# APM_BLE.net
KiCad netlist of a schematic drawn in EAGLE
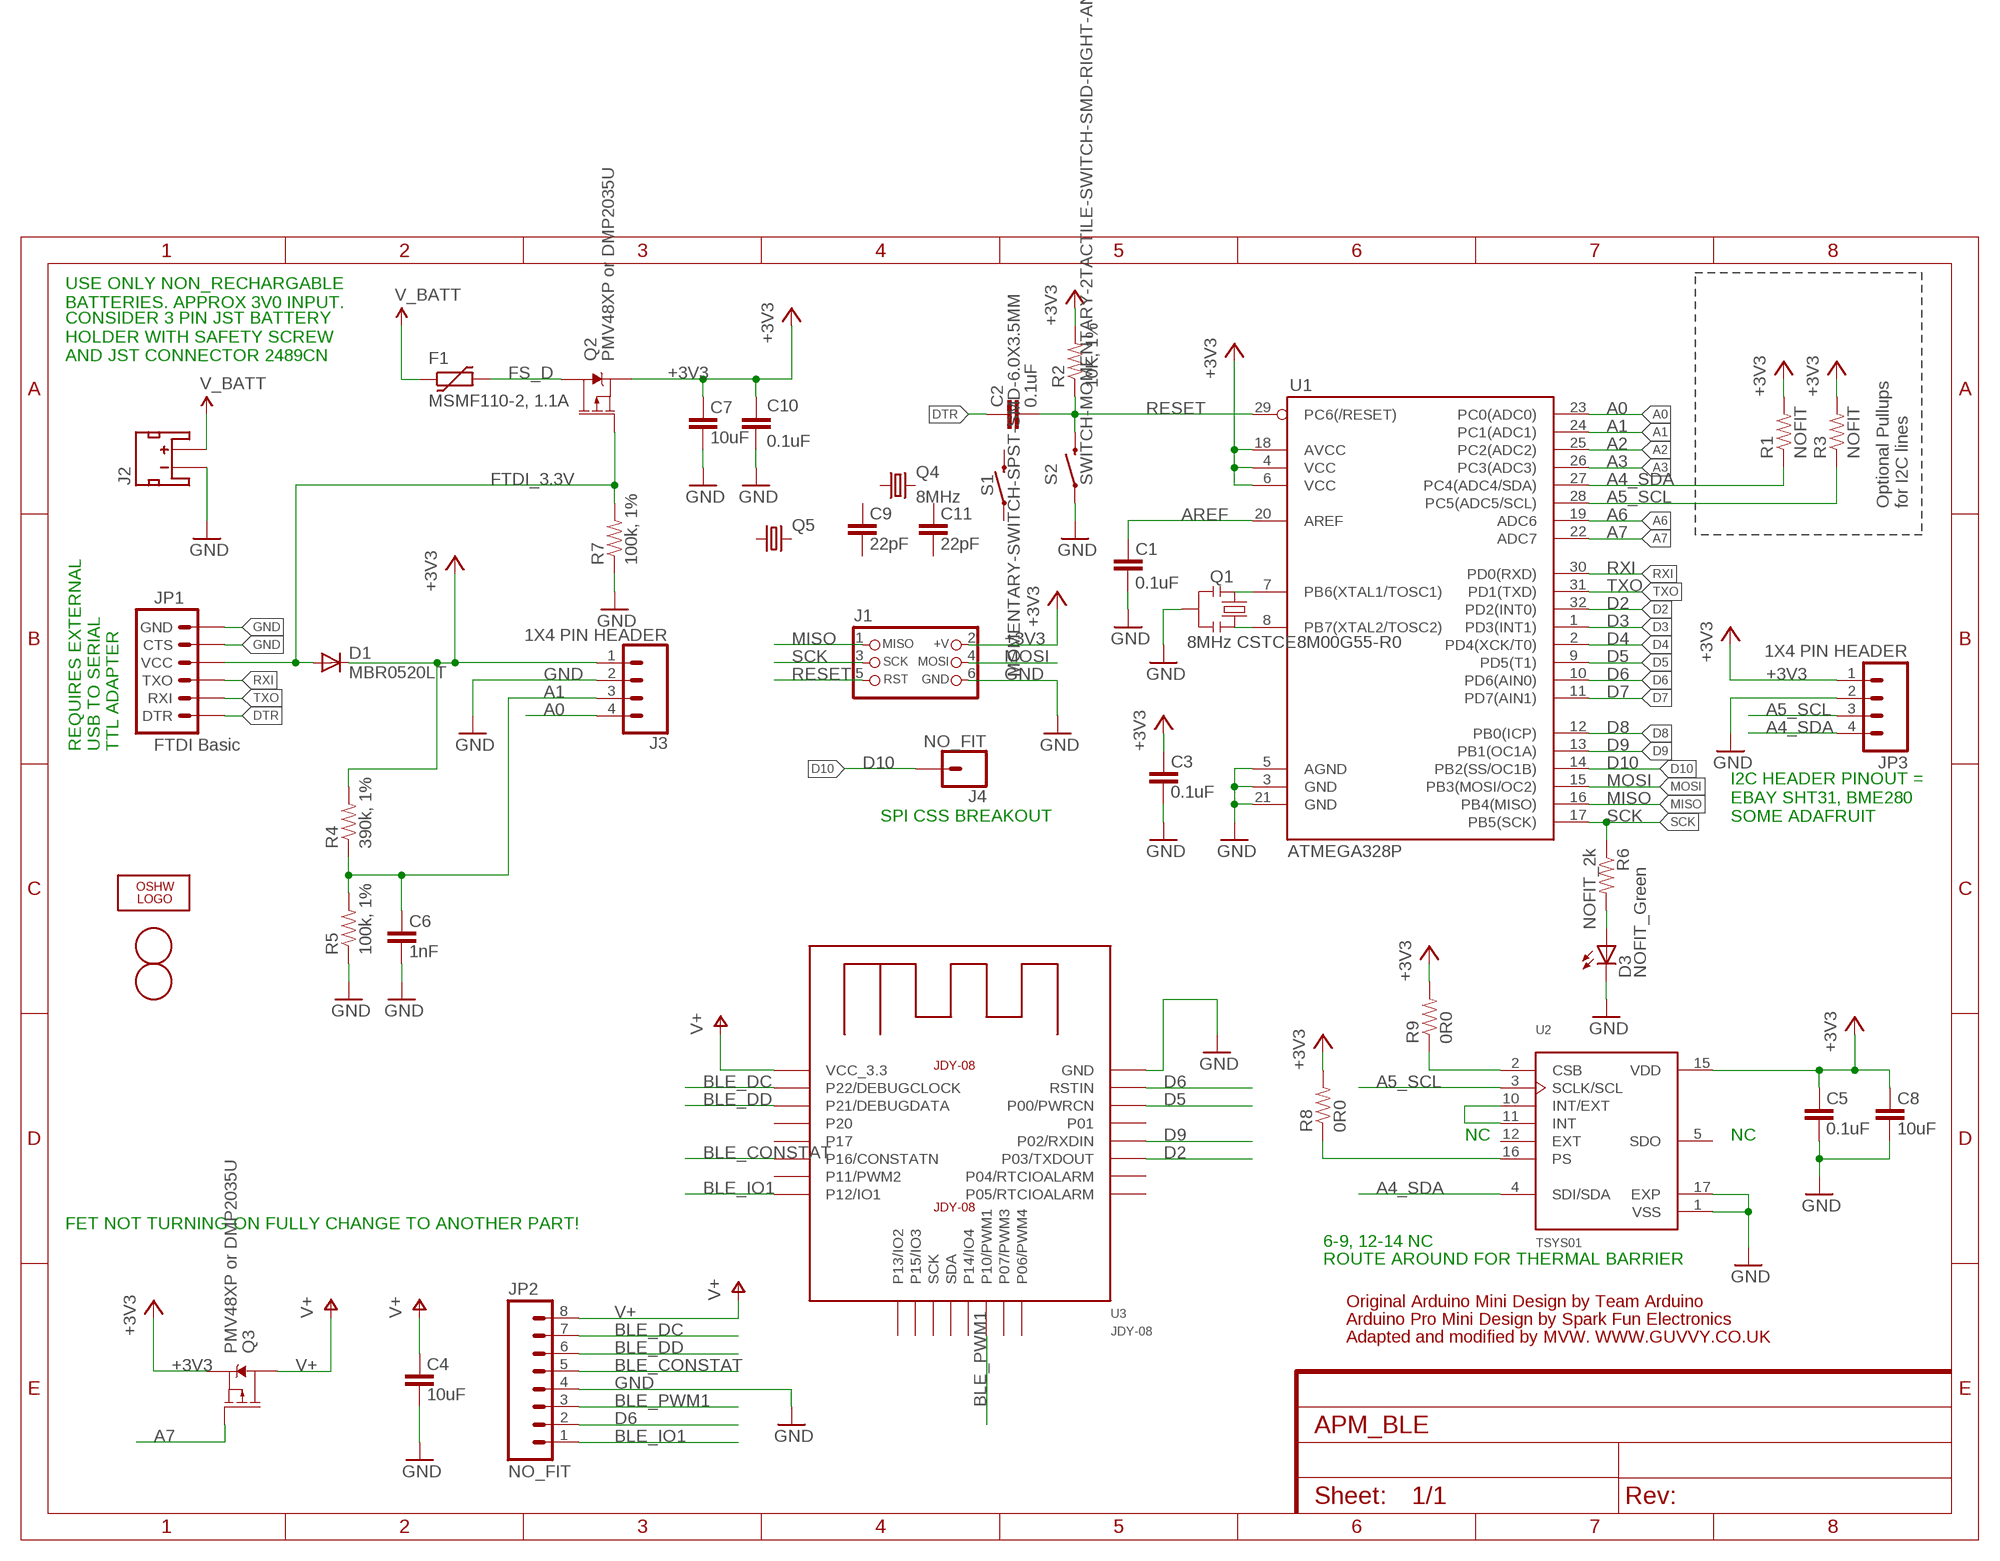
[diagram p0: schematic, sheet 1]

(export (version "E")
  (design (tool "Eeschema 10.0.6"))
  (components
    (comp (ref "C1")
      (value "0.1uF")
      (footprint "eagle-import:0603-CAP")
      (libsource (lib "eagle-import") (part "CAP0603-CAP"))
    )
    (comp (ref "C2")
      (value "0.1uF")
      (footprint "eagle-import:0603-CAP")
      (libsource (lib "eagle-import") (part "CAP0603-CAP"))
    )
    (comp (ref "C3")
      (value "0.1uF")
      (footprint "eagle-import:0603-CAP")
      (libsource (lib "eagle-import") (part "CAP0603-CAP"))
    )
    (comp (ref "C4")
      (value "10uF")
      (footprint "eagle-import:0603-CAP")
      (libsource (lib "eagle-import") (part "CAP0603-CAP"))
    )
    (comp (ref "C5")
      (value "0.1uF")
      (footprint "eagle-import:0603-CAP")
      (libsource (lib "eagle-import") (part "CAP0603-CAP"))
    )
    (comp (ref "C6")
      (value "1nF")
      (footprint "eagle-import:0603-CAP")
      (libsource (lib "eagle-import") (part "CAP0603-CAP"))
    )
    (comp (ref "C7")
      (value "10uF")
      (footprint "eagle-import:0603-CAP")
      (libsource (lib "eagle-import") (part "CAP0603-CAP"))
    )
    (comp (ref "C8")
      (value "10uF")
      (footprint "eagle-import:0603-CAP")
      (libsource (lib "eagle-import") (part "CAP0603-CAP"))
    )
    (comp (ref "C9")
      (value "22pF")
      (footprint "eagle-import:0603-CAP")
      (libsource (lib "eagle-import") (part "CAP0603-CAP"))
    )
    (comp (ref "C10")
      (value "0.1uF")
      (footprint "eagle-import:0603-CAP")
      (libsource (lib "eagle-import") (part "CAP0603-CAP"))
    )
    (comp (ref "C11")
      (value "22pF")
      (footprint "eagle-import:0603-CAP")
      (libsource (lib "eagle-import") (part "CAP0603-CAP"))
    )
    (comp (ref "D1")
      (value "MBR0520LT")
      (footprint "eagle-import:SOD123")
      (libsource (lib "eagle-import") (part "MBR0520LT"))
    )
    (comp (ref "D3")
      (value "NOFIT_Green")
      (footprint "eagle-import:0603-LED-ALT1")
      (libsource (lib "eagle-import") (part "LED"))
    )
    (comp (ref "F1")
      (value "MSMF110-2, 1.1A")
      (footprint "eagle-import:PTC1812L")
      (fields (field (name "MF") "BOURNS") (field (name "MPN") "MF-MSMF110-2"))
      (libsource (lib "eagle-import") (part "FUSE_PTC-1812"))
    )
    (comp (ref "FID1")
      (value "FIDUCIAL")
      (footprint "eagle-import:FIDUCIAL_1MM")
      (libsource (lib "eagle-import") (part "FIDUCIAL"))
    )
    (comp (ref "FID2")
      (value "FIDUCIAL")
      (footprint "eagle-import:FIDUCIAL_1MM")
      (libsource (lib "eagle-import") (part "FIDUCIAL"))
    )
    (comp (ref "J1")
      (value "CON_HEADER_PRG_AVR_ICSP-PTH")
      (footprint "eagle-import:HEADER_PRG_2X03")
      (libsource (lib "eagle-import") (part "CON_HEADER_PRG_AVR_ICSP-PTH"))
    )
    (comp (ref "J2")
      (value "S2B-PH-SM4-TB(LF)(SN)")
      (footprint "eagle-import:JST-2-SMD")
      (fields (field (name "MF") "JST (JAPAN SOLDERLESS TERMINALS)"))
      (libsource (lib "eagle-import") (part "JST_2MM_MALE"))
    )
    (comp (ref "J3")
      (value "1X4 PIN HEADER")
      (footprint "eagle-import:1X04")
      (libsource (lib "eagle-import") (part "CONN_04"))
    )
    (comp (ref "J4")
      (value "NO_FIT")
      (footprint "eagle-import:1X01")
      (libsource (lib "eagle-import") (part "CONN_01"))
    )
    (comp (ref "JP1")
      (value "FTDI Basic")
      (footprint "eagle-import:1X06")
      (libsource (lib "eagle-import") (part "ARDUINO_SERIAL_PROGRAMPTH"))
    )
    (comp (ref "JP2")
      (value "NO_FIT")
      (footprint "eagle-import:BM08B-SRSS-TB")
      (libsource (lib "eagle-import") (part "M08BM08B-SRSS-TB"))
    )
    (comp (ref "JP3")
      (value "1X4 PIN HEADER")
      (footprint "eagle-import:1X04")
      (libsource (lib "eagle-import") (part "M04PTH"))
    )
    (comp (ref "LOGO1")
      (value "OSHW_LOGO_FILLX0200-NT")
      (footprint "eagle-import:OSHW_FILLX200_NOTEXT")
      (libsource (lib "eagle-import") (part "OSHW_LOGO_FILLX0200-NT"))
    )
    (comp (ref "Q1")
      (value "8MHz CSTCE8M00G55-R0")
      (footprint "eagle-import:RESONATOR-SMD-1_1")
      (fields (field (name "MF") "MURATA") (field (name "MPN") "CSTCE8M00G55-R0"))
      (libsource (lib "eagle-import") (part "RESONATOR1{colon}1"))
    )
    (comp (ref "Q2")
      (value "PMV48XP or DMP2035U")
      (footprint "eagle-import:SOT23-3")
      (fields (field (name "MF") "DIODES INC.") (field (name "MPN") "DMP2035U"))
      (libsource (lib "eagle-import") (part "MOSFET_PCH-IRLML2244"))
    )
    (comp (ref "Q3")
      (value "PMV48XP or DMP2035U")
      (footprint "eagle-import:SOT23-3")
      (fields (field (name "MF") "DIODES INC.") (field (name "MPN") "DMP2035U"))
      (libsource (lib "eagle-import") (part "MOSFET_PCH-IRLML2244"))
    )
    (comp (ref "Q4")
      (value "8MHz")
      (footprint "eagle-import:HC49UP")
      (libsource (lib "eagle-import") (part "CRYSTALHC49UP"))
    )
    (comp (ref "Q5")
      (value "CRYSTALCTS406")
      (footprint "eagle-import:CTS406")
      (libsource (lib "eagle-import") (part "crystal_CRYSTALCTS406"))
    )
    (comp (ref "R1")
      (value "NOFIT")
      (footprint "eagle-import:0603-RES")
      (libsource (lib "eagle-import") (part "RESISTOR0603-RES"))
    )
    (comp (ref "R2")
      (value "10K, 1%")
      (footprint "eagle-import:0603-RES")
      (libsource (lib "eagle-import") (part "RESISTOR0603-RES"))
    )
    (comp (ref "R3")
      (value "NOFIT")
      (footprint "eagle-import:0603-RES")
      (libsource (lib "eagle-import") (part "RESISTOR0603-RES"))
    )
    (comp (ref "R4")
      (value "390k, 1%")
      (footprint "eagle-import:0603-RES")
      (libsource (lib "eagle-import") (part "RESISTOR0603-RES"))
    )
    (comp (ref "R5")
      (value "100k, 1%")
      (footprint "eagle-import:0603-RES")
      (libsource (lib "eagle-import") (part "RESISTOR0603-RES"))
    )
    (comp (ref "R6")
      (value "NOFIT_2k")
      (footprint "eagle-import:0603-RES")
      (libsource (lib "eagle-import") (part "RESISTOR0603-RES"))
    )
    (comp (ref "R7")
      (value "100k, 1%")
      (footprint "eagle-import:0603-RES")
      (libsource (lib "eagle-import") (part "RESISTOR0603-RES"))
    )
    (comp (ref "R8")
      (value "0R0")
      (footprint "eagle-import:0603-RES")
      (libsource (lib "eagle-import") (part "RESISTOR0603-RES"))
    )
    (comp (ref "R9")
      (value "0R0")
      (footprint "eagle-import:0603-RES")
      (libsource (lib "eagle-import") (part "RESISTOR0603-RES"))
    )
    (comp (ref "S1")
      (value "MOMENTARY-SWITCH-SPST-SMD-6.0X3.5MM")
      (footprint "eagle-import:TACTILE_SWITCH_SMD_6.0X3.5MM")
      (libsource (lib "eagle-import") (part "MOMENTARY-SWITCH-SPST-SMD-6.0X3.5MM"))
    )
    (comp (ref "S2")
      (value "SWITCH-MOMENTARY-2TACTILE-SWITCH-SMD-RIGHT-ANGLE")
      (footprint "eagle-import:TACTILE_SWITCH-SMD-RIGHT-ANGLE")
      (libsource (lib "eagle-import") (part "SWITCH-MOMENTARY-2TACTILE-SWITCH-SMD-RIGHT-ANGLE"))
    )
    (comp (ref "U1")
      (value "ATMEGA328P")
      (footprint "eagle-import:TQFP32-08")
      (fields (field (name "MF") "MICROCHIP") (field (name "MPN") "ATMEGA328P-AU"))
      (libsource (lib "eagle-import") (part "ATMEGA168"))
    )
    (comp (ref "U2")
      (value "TSYS01")
      (footprint "eagle-import:QFN65P400X400X90-17N")
      (fields (field (name "MF") "TE Connectivity"))
      (libsource (lib "eagle-import") (part "TSYS01"))
    )
    (comp (ref "U3")
      (value "JDY-08")
      (footprint "eagle-import:JDY-08")
      (libsource (lib "eagle-import") (part "JDY-08JDY-08_MODULE"))
    )
  )
  (nets
    (net (code "1") (name "+3V3") (class "Default")
      (node (ref "C10") (pin "1") (pinfunction "1_1") (pintype "passive"))
      (node (ref "C3") (pin "2") (pinfunction "2_2") (pintype "passive"))
      (node (ref "C5") (pin "2") (pinfunction "2_2") (pintype "passive"))
      (node (ref "C7") (pin "2") (pinfunction "2_2") (pintype "passive"))
      (node (ref "C8") (pin "2") (pinfunction "2_2") (pintype "passive"))
      (node (ref "D1") (pin "C") (pinfunction "C_C") (pintype "passive"))
      (node (ref "J1") (pin "2") (pinfunction "+V_2") (pintype "passive"))
      (node (ref "J3") (pin "1") (pinfunction "1_1") (pintype "passive"))
      (node (ref "JP3") (pin "1") (pinfunction "1_1") (pintype "passive"))
      (node (ref "Q2") (pin "2") (pinfunction "S_2") (pintype "bidirectional"))
      (node (ref "Q3") (pin "2") (pinfunction "S_2") (pintype "bidirectional"))
      (node (ref "R1") (pin "2") (pinfunction "2_2") (pintype "passive"))
      (node (ref "R2") (pin "2") (pinfunction "2_2") (pintype "passive"))
      (node (ref "R3") (pin "2") (pinfunction "2_2") (pintype "passive"))
      (node (ref "R4") (pin "2") (pinfunction "2_2") (pintype "passive"))
      (node (ref "R8") (pin "2") (pinfunction "2_2") (pintype "passive"))
      (node (ref "R9") (pin "2") (pinfunction "2_2") (pintype "passive"))
      (node (ref "U1") (pin "18") (pinfunction "AVCC_18") (pintype "bidirectional"))
      (node (ref "U1") (pin "4") (pinfunction "VCC_4") (pintype "bidirectional"))
      (node (ref "U1") (pin "6") (pinfunction "VCC_6") (pintype "bidirectional"))
      (node (ref "U2") (pin "15") (pinfunction "VDD_15") (pintype "power_in"))
    )
    (net (code "2") (name "/A4_SDA") (class "Default")
      (node (ref "JP3") (pin "4") (pinfunction "4_4") (pintype "passive"))
      (node (ref "R1") (pin "1") (pinfunction "1_1") (pintype "passive"))
      (node (ref "U1") (pin "27") (pinfunction "PC4(ADC4/SDA)_27") (pintype "bidirectional"))
      (node (ref "U2") (pin "4") (pinfunction "SDI/SDA_4") (pintype "bidirectional"))
    )
    (net (code "3") (name "/A5_SCL") (class "Default")
      (node (ref "JP3") (pin "3") (pinfunction "3_3") (pintype "passive"))
      (node (ref "R3") (pin "1") (pinfunction "1_1") (pintype "passive"))
      (node (ref "U1") (pin "28") (pinfunction "PC5(ADC5/SCL)_28") (pintype "bidirectional"))
      (node (ref "U2") (pin "3") (pinfunction "SCLK/SCL_3") (pintype "input"))
    )
    (net (code "4") (name "/AREF") (class "Default")
      (node (ref "C1") (pin "2") (pinfunction "2_2") (pintype "passive"))
      (node (ref "U1") (pin "20") (pinfunction "AREF_20") (pintype "bidirectional"))
    )
    (net (code "5") (name "/BLE_CONSTAT") (class "Default")
      (node (ref "JP2") (pin "5") (pinfunction "5_5") (pintype "passive"))
      (node (ref "U3") (pin "6") (pinfunction "P16/CONSTATN_6") (pintype "bidirectional"))
    )
    (net (code "6") (name "/BLE_DC") (class "Default")
      (node (ref "JP2") (pin "7") (pinfunction "7_7") (pintype "passive"))
      (node (ref "U3") (pin "2") (pinfunction "P22/DEBUGCLOCK_2") (pintype "bidirectional"))
    )
    (net (code "7") (name "/BLE_DD") (class "Default")
      (node (ref "JP2") (pin "6") (pinfunction "6_6") (pintype "passive"))
      (node (ref "U3") (pin "3") (pinfunction "P21/DEBUGDATA_3") (pintype "bidirectional"))
    )
    (net (code "8") (name "/BLE_IO1") (class "Default")
      (node (ref "JP2") (pin "1") (pinfunction "1_1") (pintype "passive"))
      (node (ref "U3") (pin "8") (pinfunction "P12/IO1_8") (pintype "bidirectional"))
    )
    (net (code "9") (name "/BLE_PWM1") (class "Default")
      (node (ref "JP2") (pin "3") (pinfunction "3_3") (pintype "passive"))
      (node (ref "U3") (pin "14") (pinfunction "P10/PWM1_14") (pintype "bidirectional"))
    )
    (net (code "10") (name "/FS_D") (class "Default")
      (node (ref "F1") (pin "2") (pinfunction "2_2") (pintype "passive"))
      (node (ref "Q2") (pin "3") (pinfunction "D_3") (pintype "bidirectional"))
    )
    (net (code "11") (name "/FTDI_3.3V") (class "Default")
      (node (ref "D1") (pin "A") (pinfunction "A_A") (pintype "passive"))
      (node (ref "JP1") (pin "4") (pinfunction "VCC_4") (pintype "passive"))
      (node (ref "Q2") (pin "1") (pinfunction "G_1") (pintype "bidirectional"))
      (node (ref "R7") (pin "2") (pinfunction "2_2") (pintype "passive"))
    )
    (net (code "12") (name "/RESET") (class "Default")
      (node (ref "C2") (pin "1") (pinfunction "1_1") (pintype "passive"))
      (node (ref "J1") (pin "5") (pinfunction "RST_5") (pintype "passive"))
      (node (ref "R2") (pin "1") (pinfunction "1_1") (pintype "passive"))
      (node (ref "S2") (pin "2") (pinfunction "2_2") (pintype "passive"))
      (node (ref "U1") (pin "29") (pinfunction "PC6(/RESET)_29") (pintype "bidirectional"))
    )
    (net (code "13") (name "A0") (class "Default")
      (node (ref "J3") (pin "4") (pinfunction "4_4") (pintype "passive"))
      (node (ref "U1") (pin "23") (pinfunction "PC0(ADC0)_23") (pintype "bidirectional"))
    )
    (net (code "14") (name "A1") (class "Default")
      (node (ref "C6") (pin "2") (pinfunction "2_2") (pintype "passive"))
      (node (ref "J3") (pin "3") (pinfunction "3_3") (pintype "passive"))
      (node (ref "R4") (pin "1") (pinfunction "1_1") (pintype "passive"))
      (node (ref "R5") (pin "2") (pinfunction "2_2") (pintype "passive"))
      (node (ref "U1") (pin "24") (pinfunction "PC1(ADC1)_24") (pintype "bidirectional"))
    )
    (net (code "15") (name "A2") (class "Default")
      (node (ref "U1") (pin "25") (pinfunction "PC2(ADC2)_25") (pintype "bidirectional"))
    )
    (net (code "16") (name "A3") (class "Default")
      (node (ref "U1") (pin "26") (pinfunction "PC3(ADC3)_26") (pintype "bidirectional"))
    )
    (net (code "17") (name "A6") (class "Default")
      (node (ref "U1") (pin "19") (pinfunction "ADC6_19") (pintype "bidirectional"))
    )
    (net (code "18") (name "A7") (class "Default")
      (node (ref "Q3") (pin "1") (pinfunction "G_1") (pintype "bidirectional"))
      (node (ref "U1") (pin "22") (pinfunction "ADC7_22") (pintype "bidirectional"))
    )
    (net (code "19") (name "D2") (class "Default")
      (node (ref "U1") (pin "32") (pinfunction "PD2(INT0)_32") (pintype "bidirectional"))
      (node (ref "U3") (pin "19") (pinfunction "P03/TXDOUT_19") (pintype "bidirectional"))
    )
    (net (code "20") (name "D3") (class "Default")
      (node (ref "U1") (pin "1") (pinfunction "PD3(INT1)_1") (pintype "bidirectional"))
    )
    (net (code "21") (name "D4") (class "Default")
      (node (ref "U1") (pin "2") (pinfunction "PD4(XCK/T0)_2") (pintype "bidirectional"))
    )
    (net (code "22") (name "D5") (class "Default")
      (node (ref "U1") (pin "9") (pinfunction "PD5(T1)_9") (pintype "bidirectional"))
      (node (ref "U3") (pin "22") (pinfunction "P00/PWRCN_22") (pintype "bidirectional"))
    )
    (net (code "23") (name "D6") (class "Default")
      (node (ref "JP2") (pin "2") (pinfunction "2_2") (pintype "passive"))
      (node (ref "U1") (pin "10") (pinfunction "PD6(AIN0)_10") (pintype "bidirectional"))
      (node (ref "U3") (pin "23") (pinfunction "RSTIN_23") (pintype "bidirectional"))
    )
    (net (code "24") (name "D7") (class "Default")
      (node (ref "U1") (pin "11") (pinfunction "PD7(AIN1)_11") (pintype "bidirectional"))
    )
    (net (code "25") (name "D8") (class "Default")
      (node (ref "U1") (pin "12") (pinfunction "PB0(ICP)_12") (pintype "bidirectional"))
    )
    (net (code "26") (name "D9") (class "Default")
      (node (ref "U1") (pin "13") (pinfunction "PB1(OC1A)_13") (pintype "bidirectional"))
      (node (ref "U3") (pin "20") (pinfunction "P02/RXDIN_20") (pintype "bidirectional"))
    )
    (net (code "27") (name "D10") (class "Default")
      (node (ref "J4") (pin "1") (pinfunction "1_1") (pintype "passive"))
      (node (ref "U1") (pin "14") (pinfunction "PB2(SS/OC1B)_14") (pintype "bidirectional"))
    )
    (net (code "28") (name "DTR") (class "Default")
      (node (ref "C2") (pin "2") (pinfunction "2_2") (pintype "passive"))
      (node (ref "JP1") (pin "1") (pinfunction "DTR_1") (pintype "passive"))
    )
    (net (code "29") (name "GND") (class "Default")
      (node (ref "C1") (pin "1") (pinfunction "1_1") (pintype "passive"))
      (node (ref "C10") (pin "2") (pinfunction "2_2") (pintype "passive"))
      (node (ref "C3") (pin "1") (pinfunction "1_1") (pintype "passive"))
      (node (ref "C4") (pin "1") (pinfunction "1_1") (pintype "passive"))
      (node (ref "C5") (pin "1") (pinfunction "1_1") (pintype "passive"))
      (node (ref "C6") (pin "1") (pinfunction "1_1") (pintype "passive"))
      (node (ref "C7") (pin "1") (pinfunction "1_1") (pintype "passive"))
      (node (ref "C8") (pin "1") (pinfunction "1_1") (pintype "passive"))
      (node (ref "D3") (pin "C") (pinfunction "C_C") (pintype "passive"))
      (node (ref "J1") (pin "6") (pinfunction "GND_6") (pintype "passive"))
      (node (ref "J2") (pin "1") (pinfunction "-_1") (pintype "bidirectional"))
      (node (ref "J3") (pin "2") (pinfunction "2_2") (pintype "passive"))
      (node (ref "JP1") (pin "5") (pinfunction "CTS_5") (pintype "passive"))
      (node (ref "JP1") (pin "6") (pinfunction "GND_6") (pintype "passive"))
      (node (ref "JP2") (pin "4") (pinfunction "4_4") (pintype "passive"))
      (node (ref "JP3") (pin "2") (pinfunction "2_2") (pintype "passive"))
      (node (ref "Q1") (pin "2") (pinfunction "2_2") (pintype "passive"))
      (node (ref "R5") (pin "1") (pinfunction "1_1") (pintype "passive"))
      (node (ref "R7") (pin "1") (pinfunction "1_1") (pintype "passive"))
      (node (ref "S2") (pin "1") (pinfunction "1_1") (pintype "passive"))
      (node (ref "U1") (pin "21") (pinfunction "GND_21") (pintype "bidirectional"))
      (node (ref "U1") (pin "3") (pinfunction "GND_3") (pintype "bidirectional"))
      (node (ref "U1") (pin "5") (pinfunction "AGND_5") (pintype "bidirectional"))
      (node (ref "U2") (pin "1") (pinfunction "VSS_1") (pintype "power_in"))
      (node (ref "U2") (pin "17") (pinfunction "EXP_17") (pintype "power_in"))
      (node (ref "U3") (pin "24") (pinfunction "GND_24") (pintype "bidirectional"))
    )
    (net (code "30") (name "MISO") (class "Default")
      (node (ref "J1") (pin "1") (pinfunction "MISO_1") (pintype "passive"))
      (node (ref "U1") (pin "16") (pinfunction "PB4(MISO)_16") (pintype "bidirectional"))
    )
    (net (code "31") (name "MOSI") (class "Default")
      (node (ref "J1") (pin "4") (pinfunction "MOSI_4") (pintype "passive"))
      (node (ref "U1") (pin "15") (pinfunction "PB3(MOSI/OC2)_15") (pintype "bidirectional"))
    )
    (net (code "32") (name "Net-(D3-PadA)") (class "Default")
      (node (ref "D3") (pin "A") (pinfunction "A_A") (pintype "passive"))
      (node (ref "R6") (pin "2") (pinfunction "2_2") (pintype "passive"))
    )
    (net (code "33") (name "Net-(U1-PB6(XTAL1{slash}TOSC1))") (class "Default")
      (node (ref "Q1") (pin "1") (pinfunction "1_1") (pintype "passive"))
      (node (ref "U1") (pin "7") (pinfunction "PB6(XTAL1/TOSC1)_7") (pintype "bidirectional"))
    )
    (net (code "34") (name "Net-(U1-PB7(XTAL2{slash}TOSC2))") (class "Default")
      (node (ref "Q1") (pin "3") (pinfunction "3_3") (pintype "passive"))
      (node (ref "U1") (pin "8") (pinfunction "PB7(XTAL2/TOSC2)_8") (pintype "bidirectional"))
    )
    (net (code "35") (name "Net-(U2-CSB)") (class "Default")
      (node (ref "R9") (pin "1") (pinfunction "1_1") (pintype "passive"))
      (node (ref "U2") (pin "2") (pinfunction "CSB_2") (pintype "input"))
    )
    (net (code "36") (name "Net-(U2-INT)") (class "Default")
      (node (ref "U2") (pin "10") (pinfunction "INT/EXT_10") (pintype "input"))
      (node (ref "U2") (pin "11") (pinfunction "INT_11") (pintype "input"))
    )
    (net (code "37") (name "Net-(U2-PS)") (class "Default")
      (node (ref "R8") (pin "1") (pinfunction "1_1") (pintype "passive"))
      (node (ref "U2") (pin "16") (pinfunction "PS_16") (pintype "input"))
    )
    (net (code "38") (name "RXI") (class "Default")
      (node (ref "JP1") (pin "3") (pinfunction "TXO_3") (pintype "passive"))
      (node (ref "U1") (pin "30") (pinfunction "PD0(RXD)_30") (pintype "bidirectional"))
    )
    (net (code "39") (name "SCK") (class "Default")
      (node (ref "J1") (pin "3") (pinfunction "SCK_3") (pintype "passive"))
      (node (ref "R6") (pin "1") (pinfunction "1_1") (pintype "passive"))
      (node (ref "U1") (pin "17") (pinfunction "PB5(SCK)_17") (pintype "bidirectional"))
    )
    (net (code "40") (name "TXO") (class "Default")
      (node (ref "JP1") (pin "2") (pinfunction "RXI_2") (pintype "passive"))
      (node (ref "U1") (pin "31") (pinfunction "PD1(TXD)_31") (pintype "bidirectional"))
    )
    (net (code "41") (name "V+") (class "Default")
      (node (ref "C4") (pin "2") (pinfunction "2_2") (pintype "passive"))
      (node (ref "JP2") (pin "8") (pinfunction "8_8") (pintype "passive"))
      (node (ref "Q3") (pin "3") (pinfunction "D_3") (pintype "bidirectional"))
      (node (ref "U3") (pin "1") (pinfunction "VCC_3.3_1") (pintype "bidirectional"))
    )
    (net (code "42") (name "V_BATT") (class "Default")
      (node (ref "F1") (pin "1") (pinfunction "1_1") (pintype "passive"))
      (node (ref "J2") (pin "2") (pinfunction "+_2") (pintype "bidirectional"))
    )
    (net (code "43") (name "unconnected-(C9-Pad1)") (class "Default")
      (node (ref "C9") (pin "1") (pinfunction "1_1") (pintype "passive"))
    )
    (net (code "44") (name "unconnected-(C9-Pad2)") (class "Default")
      (node (ref "C9") (pin "2") (pinfunction "2_2") (pintype "passive"))
    )
    (net (code "45") (name "unconnected-(C11-Pad1)") (class "Default")
      (node (ref "C11") (pin "1") (pinfunction "1_1") (pintype "passive"))
    )
    (net (code "46") (name "unconnected-(C11-Pad2)") (class "Default")
      (node (ref "C11") (pin "2") (pinfunction "2_2") (pintype "passive"))
    )
    (net (code "47") (name "unconnected-(J2-PAD1-PadNC1)") (class "Default")
      (node (ref "J2") (pin "NC1") (pinfunction "PAD1_NC1") (pintype "bidirectional"))
    )
    (net (code "48") (name "unconnected-(J2-PAD2-PadNC2)") (class "Default")
      (node (ref "J2") (pin "NC2") (pinfunction "PAD2_NC2") (pintype "bidirectional"))
    )
    (net (code "49") (name "unconnected-(Q4-Pad1)") (class "Default")
      (node (ref "Q4") (pin "1") (pinfunction "1_1") (pintype "passive"))
    )
    (net (code "50") (name "unconnected-(Q4-Pad2)") (class "Default")
      (node (ref "Q4") (pin "2") (pinfunction "2_2") (pintype "passive"))
    )
    (net (code "51") (name "unconnected-(Q5-2-Pad3)") (class "Default")
      (node (ref "Q5") (pin "3") (pinfunction "2_3") (pintype "passive"))
    )
    (net (code "52") (name "unconnected-(Q5-Pad1)") (class "Default")
      (node (ref "Q5") (pin "1") (pinfunction "1_1") (pintype "passive"))
    )
    (net (code "53") (name "unconnected-(S1-Pad1)") (class "Default")
      (node (ref "S1") (pin "1") (pinfunction "1_1") (pintype "passive"))
    )
    (net (code "54") (name "unconnected-(S1-Pad2)") (class "Default")
      (node (ref "S1") (pin "2") (pinfunction "2_2") (pintype "passive"))
    )
    (net (code "55") (name "unconnected-(U2-EXT-Pad12)") (class "Default")
      (node (ref "U2") (pin "12") (pinfunction "EXT_12") (pintype "input"))
    )
    (net (code "56") (name "unconnected-(U2-SDO-Pad5)") (class "Default")
      (node (ref "U2") (pin "5") (pinfunction "SDO_5") (pintype "output"))
    )
    (net (code "57") (name "unconnected-(U3-P01-Pad21)") (class "Default")
      (node (ref "U3") (pin "21") (pinfunction "P01_21") (pintype "bidirectional"))
    )
    (net (code "58") (name "unconnected-(U3-P04{slash}RTCIOALARM-Pad18)") (class "Default")
      (node (ref "U3") (pin "18") (pinfunction "P04/RTCIOALARM_18") (pintype "bidirectional"))
    )
    (net (code "59") (name "unconnected-(U3-P05{slash}RTCIOALARM-Pad17)") (class "Default")
      (node (ref "U3") (pin "17") (pinfunction "P05/RTCIOALARM_17") (pintype "bidirectional"))
    )
    (net (code "60") (name "unconnected-(U3-P06{slash}PWM4-Pad16)") (class "Default")
      (node (ref "U3") (pin "16") (pinfunction "P06/PWM4_16") (pintype "bidirectional"))
    )
    (net (code "61") (name "unconnected-(U3-P07{slash}PWM3-Pad15)") (class "Default")
      (node (ref "U3") (pin "15") (pinfunction "P07/PWM3_15") (pintype "bidirectional"))
    )
    (net (code "62") (name "unconnected-(U3-P11{slash}PWM2-Pad7)") (class "Default")
      (node (ref "U3") (pin "7") (pinfunction "P11/PWM2_7") (pintype "bidirectional"))
    )
    (net (code "63") (name "unconnected-(U3-P13{slash}IO2-Pad9)") (class "Default")
      (node (ref "U3") (pin "9") (pinfunction "P13/IO2_9") (pintype "bidirectional"))
    )
    (net (code "64") (name "unconnected-(U3-P14{slash}IO4-Pad13)") (class "Default")
      (node (ref "U3") (pin "13") (pinfunction "P14/IO4_13") (pintype "bidirectional"))
    )
    (net (code "65") (name "unconnected-(U3-P15{slash}IO3-Pad10)") (class "Default")
      (node (ref "U3") (pin "10") (pinfunction "P15/IO3_10") (pintype "bidirectional"))
    )
    (net (code "66") (name "unconnected-(U3-P17-Pad5)") (class "Default")
      (node (ref "U3") (pin "5") (pinfunction "P17_5") (pintype "bidirectional"))
    )
    (net (code "67") (name "unconnected-(U3-P20-Pad4)") (class "Default")
      (node (ref "U3") (pin "4") (pinfunction "P20_4") (pintype "bidirectional"))
    )
    (net (code "68") (name "unconnected-(U3-SCK-Pad11)") (class "Default")
      (node (ref "U3") (pin "11") (pinfunction "SCK_11") (pintype "bidirectional"))
    )
    (net (code "69") (name "unconnected-(U3-SDA-Pad12)") (class "Default")
      (node (ref "U3") (pin "12") (pinfunction "SDA_12") (pintype "bidirectional"))
    )
  )
)
